# design.net
KiCad netlist of a schematic drawn in Altium Designer
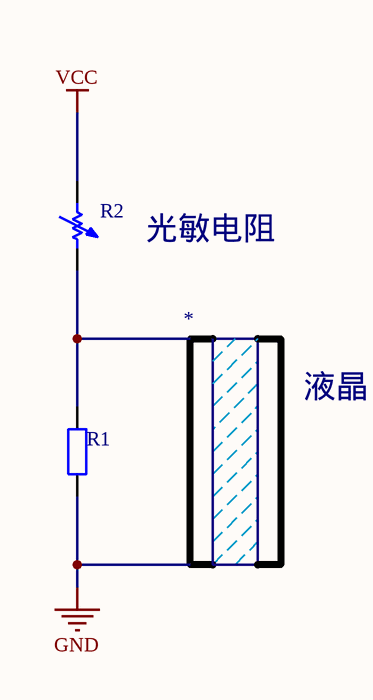
[diagram p0: 可调液晶原理图.SchDoc]

(export (version "E")
  (design (tool "Eeschema 10.0.6"))
  (components
    (comp (ref "*") (value "Component_1") (libsource (lib "液晶") (part "Component_1")))
    (comp (ref "R1")
      (value "Res2")
      (footprint "AXIAL-0.4")
      (description "Resistor")
      (fields (field (name "PUBLISHER") "Altium Limited"))
      (libsource (lib "Miscellaneous Devices") (part "Res2"))
    )
    (comp (ref "R2")
      (value "Res Adj1")
      (footprint "AXIAL-0.7")
      (description "Variable Resistor")
      (fields (field (name "PUBLISHER") "Altium Limited"))
      (libsource (lib "Miscellaneous Devices") (part "Res Adj1"))
    )
  )
  (nets
    (net (code "1") (name "GND") (class "Default")
      (node (ref "R1") (pin "1") (pinfunction "1_1") (pintype "passive"))
    )
    (net (code "2") (name "Net-(R1-Pad2)") (class "Default")
      (node (ref "R1") (pin "2") (pinfunction "2_2") (pintype "passive"))
      (node (ref "R2") (pin "2") (pinfunction "2_2") (pintype "passive"))
    )
    (net (code "3") (name "VCC") (class "Default")
      (node (ref "R2") (pin "1") (pinfunction "1_1") (pintype "passive"))
    )
  )
)
